# Photon_Proto_Shield.net
KiCad netlist of a schematic drawn in EAGLE
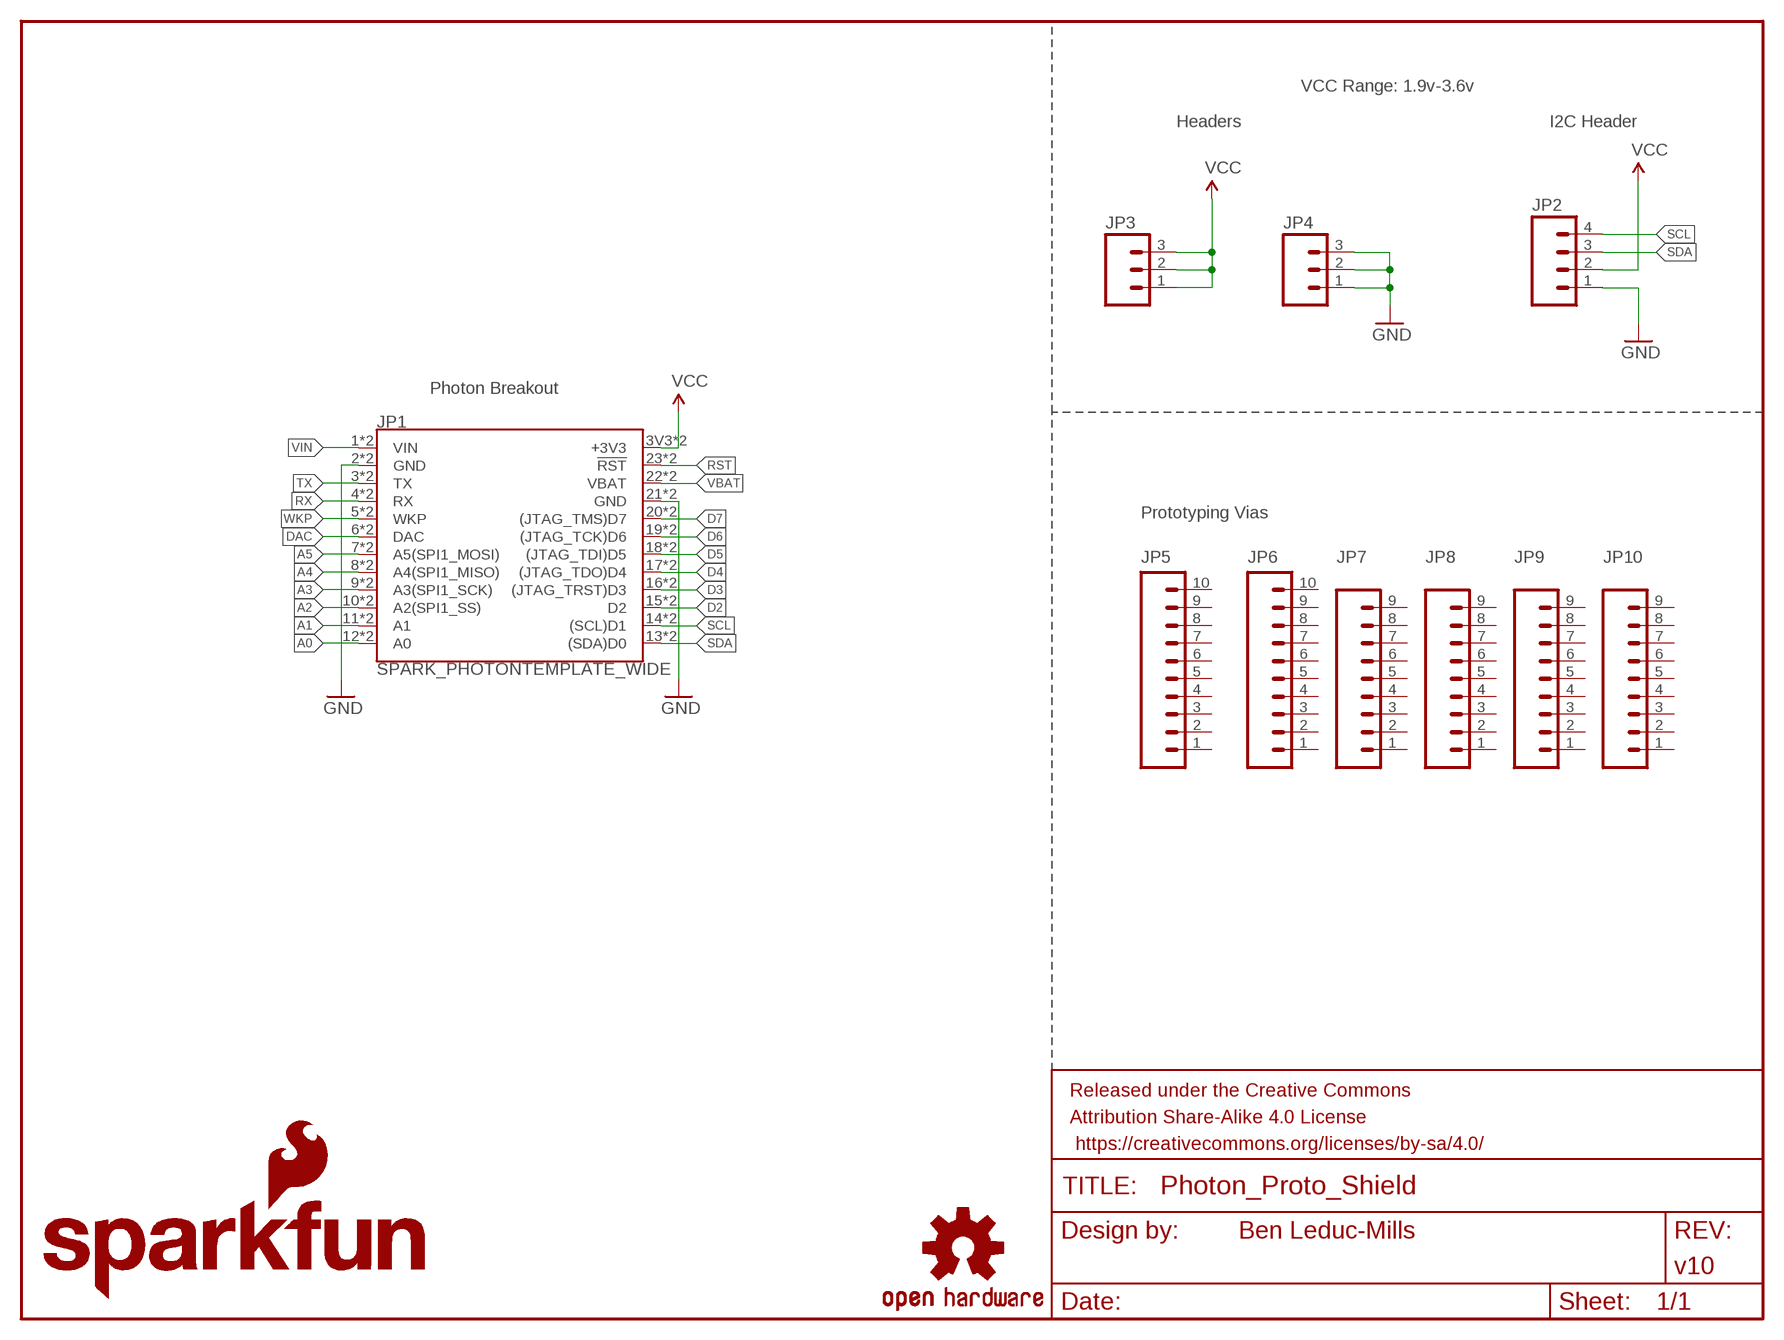
[diagram p0: schematic, sheet 1]

(export (version "E")
  (design (tool "Eeschema 10.0.6"))
  (components
    (comp (ref "FRAME1")
      (value "FRAME-LETTER")
      (footprint "eagle-import:CREATIVE_COMMONS")
      (fields (field (name "DESIGNER") "Ben Leduc-Mills") (field (name "VERSION") "v10"))
      (libsource (lib "eagle-import") (part "FRAME-LETTER"))
    )
    (comp (ref "JP1")
      (value "SPARK_PHOTONTEMPLATE_WIDE")
      (footprint "eagle-import:SPARK_PHOTON_TEMPLATE_WIDE")
      (libsource (lib "eagle-import") (part "SPARK_PHOTONTEMPLATE_WIDE"))
    )
    (comp (ref "JP2")
      (value "M04PTH")
      (footprint "eagle-import:1X04")
      (libsource (lib "eagle-import") (part "M04PTH"))
    )
    (comp (ref "JP3")
      (value "M03PTH")
      (footprint "eagle-import:1X03")
      (libsource (lib "eagle-import") (part "M03PTH"))
    )
    (comp (ref "JP4")
      (value "M03PTH")
      (footprint "eagle-import:1X03")
      (libsource (lib "eagle-import") (part "M03PTH"))
    )
    (comp (ref "JP5")
      (value "M10NO_SILK_PTH_FEMALE")
      (footprint "eagle-import:1X10_NO_SILK")
      (libsource (lib "eagle-import") (part "M10NO_SILK_PTH_FEMALE"))
    )
    (comp (ref "JP6")
      (value "M10NO_SILK_PTH_FEMALE")
      (footprint "eagle-import:1X10_NO_SILK")
      (libsource (lib "eagle-import") (part "M10NO_SILK_PTH_FEMALE"))
    )
    (comp (ref "JP7")
      (value "M09NO_SILK")
      (footprint "eagle-import:1X09_NO_SILK")
      (libsource (lib "eagle-import") (part "M09NO_SILK"))
    )
    (comp (ref "JP8")
      (value "M09NO_SILK")
      (footprint "eagle-import:1X09_NO_SILK")
      (libsource (lib "eagle-import") (part "M09NO_SILK"))
    )
    (comp (ref "JP9")
      (value "M09NO_SILK")
      (footprint "eagle-import:1X09_NO_SILK")
      (libsource (lib "eagle-import") (part "M09NO_SILK"))
    )
    (comp (ref "JP10")
      (value "M09NO_SILK")
      (footprint "eagle-import:1X09_NO_SILK")
      (libsource (lib "eagle-import") (part "M09NO_SILK"))
    )
    (comp (ref "LOGO1")
      (value "SFE_LOGO_NAME_FLAME.1_INCH")
      (footprint "eagle-import:SFE_LOGO_NAME_FLAME_.1")
      (libsource (lib "eagle-import") (part "SFE_LOGO_NAME_FLAME.1_INCH"))
    )
    (comp (ref "LOGO2")
      (value "OSHW-LOGOS")
      (footprint "eagle-import:OSHW-LOGO-S")
      (libsource (lib "eagle-import") (part "OSHW-LOGOS"))
    )
  )
  (nets
    (net (code "1") (name "A0") (class "Default")
      (node (ref "JP1") (pin "12") (pinfunction "A0_12") (pintype "bidirectional"))
      (node (ref "JP1") (pin "A0") (pinfunction "A0_A0") (pintype "bidirectional"))
    )
    (net (code "2") (name "A1") (class "Default")
      (node (ref "JP1") (pin "11") (pinfunction "A1_11") (pintype "bidirectional"))
      (node (ref "JP1") (pin "A1") (pinfunction "A1_A1") (pintype "bidirectional"))
    )
    (net (code "3") (name "A2") (class "Default")
      (node (ref "JP1") (pin "10") (pinfunction "A2(SPI1_SS)_10") (pintype "bidirectional"))
      (node (ref "JP1") (pin "A2") (pinfunction "A2(SPI1_SS)_A2") (pintype "bidirectional"))
    )
    (net (code "4") (name "A3") (class "Default")
      (node (ref "JP1") (pin "9") (pinfunction "A3(SPI1_SCK)_9") (pintype "bidirectional"))
      (node (ref "JP1") (pin "A3") (pinfunction "A3(SPI1_SCK)_A3") (pintype "bidirectional"))
    )
    (net (code "5") (name "A4") (class "Default")
      (node (ref "JP1") (pin "8") (pinfunction "A4(SPI1_MISO)_8") (pintype "bidirectional"))
      (node (ref "JP1") (pin "A4") (pinfunction "A4(SPI1_MISO)_A4") (pintype "bidirectional"))
    )
    (net (code "6") (name "A5") (class "Default")
      (node (ref "JP1") (pin "7") (pinfunction "A5(SPI1_MOSI)_7") (pintype "bidirectional"))
      (node (ref "JP1") (pin "A5") (pinfunction "A5(SPI1_MOSI)_A5") (pintype "bidirectional"))
    )
    (net (code "7") (name "D2") (class "Default")
      (node (ref "JP1") (pin "15") (pinfunction "D2_15") (pintype "bidirectional"))
      (node (ref "JP1") (pin "D2") (pinfunction "D2_D2") (pintype "bidirectional"))
    )
    (net (code "8") (name "D3") (class "Default")
      (node (ref "JP1") (pin "16") (pinfunction "(JTAG_TRST)D3_16") (pintype "bidirectional"))
      (node (ref "JP1") (pin "D3") (pinfunction "(JTAG_TRST)D3_D3") (pintype "bidirectional"))
    )
    (net (code "9") (name "D4") (class "Default")
      (node (ref "JP1") (pin "17") (pinfunction "(JTAG_TDO)D4_17") (pintype "bidirectional"))
      (node (ref "JP1") (pin "D4") (pinfunction "(JTAG_TDO)D4_D4") (pintype "bidirectional"))
    )
    (net (code "10") (name "D5") (class "Default")
      (node (ref "JP1") (pin "18") (pinfunction "(JTAG_TDI)D5_18") (pintype "bidirectional"))
      (node (ref "JP1") (pin "D5") (pinfunction "(JTAG_TDI)D5_D5") (pintype "bidirectional"))
    )
    (net (code "11") (name "D6") (class "Default")
      (node (ref "JP1") (pin "19") (pinfunction "(JTAG_TCK)D6_19") (pintype "bidirectional"))
      (node (ref "JP1") (pin "D6") (pinfunction "(JTAG_TCK)D6_D6") (pintype "bidirectional"))
    )
    (net (code "12") (name "D7") (class "Default")
      (node (ref "JP1") (pin "20") (pinfunction "(JTAG_TMS)D7_20") (pintype "bidirectional"))
      (node (ref "JP1") (pin "D7") (pinfunction "(JTAG_TMS)D7_D7") (pintype "bidirectional"))
    )
    (net (code "13") (name "DAC") (class "Default")
      (node (ref "JP1") (pin "6") (pinfunction "DAC_6") (pintype "bidirectional"))
      (node (ref "JP1") (pin "DAC") (pinfunction "DAC_DAC") (pintype "bidirectional"))
    )
    (net (code "14") (name "GND") (class "Default")
      (node (ref "JP1") (pin "2") (pinfunction "GND_2") (pintype "bidirectional"))
      (node (ref "JP1") (pin "21") (pinfunction "GND_21") (pintype "bidirectional"))
      (node (ref "JP1") (pin "GND@0") (pinfunction "GND_GND@0") (pintype "bidirectional"))
      (node (ref "JP1") (pin "GND@2") (pinfunction "GND_GND@2") (pintype "bidirectional"))
      (node (ref "JP2") (pin "1") (pinfunction "1_1") (pintype "passive"))
      (node (ref "JP4") (pin "1") (pinfunction "1_1") (pintype "passive"))
      (node (ref "JP4") (pin "2") (pinfunction "2_2") (pintype "passive"))
      (node (ref "JP4") (pin "3") (pinfunction "3_3") (pintype "passive"))
    )
    (net (code "15") (name "RST") (class "Default")
      (node (ref "JP1") (pin "23") (pinfunction "~{RST}_23") (pintype "bidirectional"))
      (node (ref "JP1") (pin "RST") (pinfunction "~{RST}_RST") (pintype "bidirectional"))
    )
    (net (code "16") (name "RX") (class "Default")
      (node (ref "JP1") (pin "4") (pinfunction "RX_4") (pintype "bidirectional"))
      (node (ref "JP1") (pin "RX") (pinfunction "RX_RX") (pintype "bidirectional"))
    )
    (net (code "17") (name "SCL") (class "Default")
      (node (ref "JP1") (pin "14") (pinfunction "(SCL)D1_14") (pintype "bidirectional"))
      (node (ref "JP1") (pin "D1") (pinfunction "(SCL)D1_D1") (pintype "bidirectional"))
      (node (ref "JP2") (pin "4") (pinfunction "4_4") (pintype "passive"))
    )
    (net (code "18") (name "SDA") (class "Default")
      (node (ref "JP1") (pin "13") (pinfunction "(SDA)D0_13") (pintype "bidirectional"))
      (node (ref "JP1") (pin "D0") (pinfunction "(SDA)D0_D0") (pintype "bidirectional"))
      (node (ref "JP2") (pin "3") (pinfunction "3_3") (pintype "passive"))
    )
    (net (code "19") (name "TX") (class "Default")
      (node (ref "JP1") (pin "3") (pinfunction "TX_3") (pintype "bidirectional"))
      (node (ref "JP1") (pin "TX") (pinfunction "TX_TX") (pintype "bidirectional"))
    )
    (net (code "20") (name "VBAT") (class "Default")
      (node (ref "JP1") (pin "22") (pinfunction "VBAT_22") (pintype "bidirectional"))
      (node (ref "JP1") (pin "VBAT") (pinfunction "VBAT_VBAT") (pintype "bidirectional"))
    )
    (net (code "21") (name "VCC") (class "Default")
      (node (ref "JP1") (pin "24") (pinfunction "+3V3_24") (pintype "bidirectional"))
      (node (ref "JP1") (pin "3V3") (pinfunction "+3V3_3V3") (pintype "bidirectional"))
      (node (ref "JP2") (pin "2") (pinfunction "2_2") (pintype "passive"))
      (node (ref "JP3") (pin "1") (pinfunction "1_1") (pintype "passive"))
      (node (ref "JP3") (pin "2") (pinfunction "2_2") (pintype "passive"))
      (node (ref "JP3") (pin "3") (pinfunction "3_3") (pintype "passive"))
    )
    (net (code "22") (name "VIN") (class "Default")
      (node (ref "JP1") (pin "1") (pinfunction "VIN_1") (pintype "bidirectional"))
      (node (ref "JP1") (pin "VIN") (pinfunction "VIN_VIN") (pintype "bidirectional"))
    )
    (net (code "23") (name "WKP") (class "Default")
      (node (ref "JP1") (pin "5") (pinfunction "WKP_5") (pintype "bidirectional"))
      (node (ref "JP1") (pin "WKP") (pinfunction "WKP_WKP") (pintype "bidirectional"))
    )
    (net (code "24") (name "unconnected-(JP5-Pad1)") (class "Default")
      (node (ref "JP5") (pin "1") (pinfunction "1_1") (pintype "passive"))
    )
    (net (code "25") (name "unconnected-(JP5-Pad2)") (class "Default")
      (node (ref "JP5") (pin "2") (pinfunction "2_2") (pintype "passive"))
    )
    (net (code "26") (name "unconnected-(JP5-Pad3)") (class "Default")
      (node (ref "JP5") (pin "3") (pinfunction "3_3") (pintype "passive"))
    )
    (net (code "27") (name "unconnected-(JP5-Pad4)") (class "Default")
      (node (ref "JP5") (pin "4") (pinfunction "4_4") (pintype "passive"))
    )
    (net (code "28") (name "unconnected-(JP5-Pad5)") (class "Default")
      (node (ref "JP5") (pin "5") (pinfunction "5_5") (pintype "passive"))
    )
    (net (code "29") (name "unconnected-(JP5-Pad6)") (class "Default")
      (node (ref "JP5") (pin "6") (pinfunction "6_6") (pintype "passive"))
    )
    (net (code "30") (name "unconnected-(JP5-Pad7)") (class "Default")
      (node (ref "JP5") (pin "7") (pinfunction "7_7") (pintype "passive"))
    )
    (net (code "31") (name "unconnected-(JP5-Pad8)") (class "Default")
      (node (ref "JP5") (pin "8") (pinfunction "8_8") (pintype "passive"))
    )
    (net (code "32") (name "unconnected-(JP5-Pad9)") (class "Default")
      (node (ref "JP5") (pin "9") (pinfunction "9_9") (pintype "passive"))
    )
    (net (code "33") (name "unconnected-(JP5-Pad10)") (class "Default")
      (node (ref "JP5") (pin "10") (pinfunction "10_10") (pintype "passive"))
    )
    (net (code "34") (name "unconnected-(JP6-Pad1)") (class "Default")
      (node (ref "JP6") (pin "1") (pinfunction "1_1") (pintype "passive"))
    )
    (net (code "35") (name "unconnected-(JP6-Pad2)") (class "Default")
      (node (ref "JP6") (pin "2") (pinfunction "2_2") (pintype "passive"))
    )
    (net (code "36") (name "unconnected-(JP6-Pad3)") (class "Default")
      (node (ref "JP6") (pin "3") (pinfunction "3_3") (pintype "passive"))
    )
    (net (code "37") (name "unconnected-(JP6-Pad4)") (class "Default")
      (node (ref "JP6") (pin "4") (pinfunction "4_4") (pintype "passive"))
    )
    (net (code "38") (name "unconnected-(JP6-Pad5)") (class "Default")
      (node (ref "JP6") (pin "5") (pinfunction "5_5") (pintype "passive"))
    )
    (net (code "39") (name "unconnected-(JP6-Pad6)") (class "Default")
      (node (ref "JP6") (pin "6") (pinfunction "6_6") (pintype "passive"))
    )
    (net (code "40") (name "unconnected-(JP6-Pad7)") (class "Default")
      (node (ref "JP6") (pin "7") (pinfunction "7_7") (pintype "passive"))
    )
    (net (code "41") (name "unconnected-(JP6-Pad8)") (class "Default")
      (node (ref "JP6") (pin "8") (pinfunction "8_8") (pintype "passive"))
    )
    (net (code "42") (name "unconnected-(JP6-Pad9)") (class "Default")
      (node (ref "JP6") (pin "9") (pinfunction "9_9") (pintype "passive"))
    )
    (net (code "43") (name "unconnected-(JP6-Pad10)") (class "Default")
      (node (ref "JP6") (pin "10") (pinfunction "10_10") (pintype "passive"))
    )
    (net (code "44") (name "unconnected-(JP7-Pad1)") (class "Default")
      (node (ref "JP7") (pin "1") (pinfunction "1_1") (pintype "passive"))
    )
    (net (code "45") (name "unconnected-(JP7-Pad2)") (class "Default")
      (node (ref "JP7") (pin "2") (pinfunction "2_2") (pintype "passive"))
    )
    (net (code "46") (name "unconnected-(JP7-Pad3)") (class "Default")
      (node (ref "JP7") (pin "3") (pinfunction "3_3") (pintype "passive"))
    )
    (net (code "47") (name "unconnected-(JP7-Pad4)") (class "Default")
      (node (ref "JP7") (pin "4") (pinfunction "4_4") (pintype "passive"))
    )
    (net (code "48") (name "unconnected-(JP7-Pad5)") (class "Default")
      (node (ref "JP7") (pin "5") (pinfunction "5_5") (pintype "passive"))
    )
    (net (code "49") (name "unconnected-(JP7-Pad6)") (class "Default")
      (node (ref "JP7") (pin "6") (pinfunction "6_6") (pintype "passive"))
    )
    (net (code "50") (name "unconnected-(JP7-Pad7)") (class "Default")
      (node (ref "JP7") (pin "7") (pinfunction "7_7") (pintype "passive"))
    )
    (net (code "51") (name "unconnected-(JP7-Pad8)") (class "Default")
      (node (ref "JP7") (pin "8") (pinfunction "8_8") (pintype "passive"))
    )
    (net (code "52") (name "unconnected-(JP7-Pad9)") (class "Default")
      (node (ref "JP7") (pin "9") (pinfunction "9_9") (pintype "passive"))
    )
    (net (code "53") (name "unconnected-(JP8-Pad1)") (class "Default")
      (node (ref "JP8") (pin "1") (pinfunction "1_1") (pintype "passive"))
    )
    (net (code "54") (name "unconnected-(JP8-Pad2)") (class "Default")
      (node (ref "JP8") (pin "2") (pinfunction "2_2") (pintype "passive"))
    )
    (net (code "55") (name "unconnected-(JP8-Pad3)") (class "Default")
      (node (ref "JP8") (pin "3") (pinfunction "3_3") (pintype "passive"))
    )
    (net (code "56") (name "unconnected-(JP8-Pad4)") (class "Default")
      (node (ref "JP8") (pin "4") (pinfunction "4_4") (pintype "passive"))
    )
    (net (code "57") (name "unconnected-(JP8-Pad5)") (class "Default")
      (node (ref "JP8") (pin "5") (pinfunction "5_5") (pintype "passive"))
    )
    (net (code "58") (name "unconnected-(JP8-Pad6)") (class "Default")
      (node (ref "JP8") (pin "6") (pinfunction "6_6") (pintype "passive"))
    )
    (net (code "59") (name "unconnected-(JP8-Pad7)") (class "Default")
      (node (ref "JP8") (pin "7") (pinfunction "7_7") (pintype "passive"))
    )
    (net (code "60") (name "unconnected-(JP8-Pad8)") (class "Default")
      (node (ref "JP8") (pin "8") (pinfunction "8_8") (pintype "passive"))
    )
    (net (code "61") (name "unconnected-(JP8-Pad9)") (class "Default")
      (node (ref "JP8") (pin "9") (pinfunction "9_9") (pintype "passive"))
    )
    (net (code "62") (name "unconnected-(JP9-Pad1)") (class "Default")
      (node (ref "JP9") (pin "1") (pinfunction "1_1") (pintype "passive"))
    )
    (net (code "63") (name "unconnected-(JP9-Pad2)") (class "Default")
      (node (ref "JP9") (pin "2") (pinfunction "2_2") (pintype "passive"))
    )
    (net (code "64") (name "unconnected-(JP9-Pad3)") (class "Default")
      (node (ref "JP9") (pin "3") (pinfunction "3_3") (pintype "passive"))
    )
    (net (code "65") (name "unconnected-(JP9-Pad4)") (class "Default")
      (node (ref "JP9") (pin "4") (pinfunction "4_4") (pintype "passive"))
    )
    (net (code "66") (name "unconnected-(JP9-Pad5)") (class "Default")
      (node (ref "JP9") (pin "5") (pinfunction "5_5") (pintype "passive"))
    )
    (net (code "67") (name "unconnected-(JP9-Pad6)") (class "Default")
      (node (ref "JP9") (pin "6") (pinfunction "6_6") (pintype "passive"))
    )
    (net (code "68") (name "unconnected-(JP9-Pad7)") (class "Default")
      (node (ref "JP9") (pin "7") (pinfunction "7_7") (pintype "passive"))
    )
    (net (code "69") (name "unconnected-(JP9-Pad8)") (class "Default")
      (node (ref "JP9") (pin "8") (pinfunction "8_8") (pintype "passive"))
    )
    (net (code "70") (name "unconnected-(JP9-Pad9)") (class "Default")
      (node (ref "JP9") (pin "9") (pinfunction "9_9") (pintype "passive"))
    )
    (net (code "71") (name "unconnected-(JP10-Pad1)") (class "Default")
      (node (ref "JP10") (pin "1") (pinfunction "1_1") (pintype "passive"))
    )
    (net (code "72") (name "unconnected-(JP10-Pad2)") (class "Default")
      (node (ref "JP10") (pin "2") (pinfunction "2_2") (pintype "passive"))
    )
    (net (code "73") (name "unconnected-(JP10-Pad3)") (class "Default")
      (node (ref "JP10") (pin "3") (pinfunction "3_3") (pintype "passive"))
    )
    (net (code "74") (name "unconnected-(JP10-Pad4)") (class "Default")
      (node (ref "JP10") (pin "4") (pinfunction "4_4") (pintype "passive"))
    )
    (net (code "75") (name "unconnected-(JP10-Pad5)") (class "Default")
      (node (ref "JP10") (pin "5") (pinfunction "5_5") (pintype "passive"))
    )
    (net (code "76") (name "unconnected-(JP10-Pad6)") (class "Default")
      (node (ref "JP10") (pin "6") (pinfunction "6_6") (pintype "passive"))
    )
    (net (code "77") (name "unconnected-(JP10-Pad7)") (class "Default")
      (node (ref "JP10") (pin "7") (pinfunction "7_7") (pintype "passive"))
    )
    (net (code "78") (name "unconnected-(JP10-Pad8)") (class "Default")
      (node (ref "JP10") (pin "8") (pinfunction "8_8") (pintype "passive"))
    )
    (net (code "79") (name "unconnected-(JP10-Pad9)") (class "Default")
      (node (ref "JP10") (pin "9") (pinfunction "9_9") (pintype "passive"))
    )
  )
)
